# feld_hw.net
KiCad netlist of a schematic drawn in EAGLE
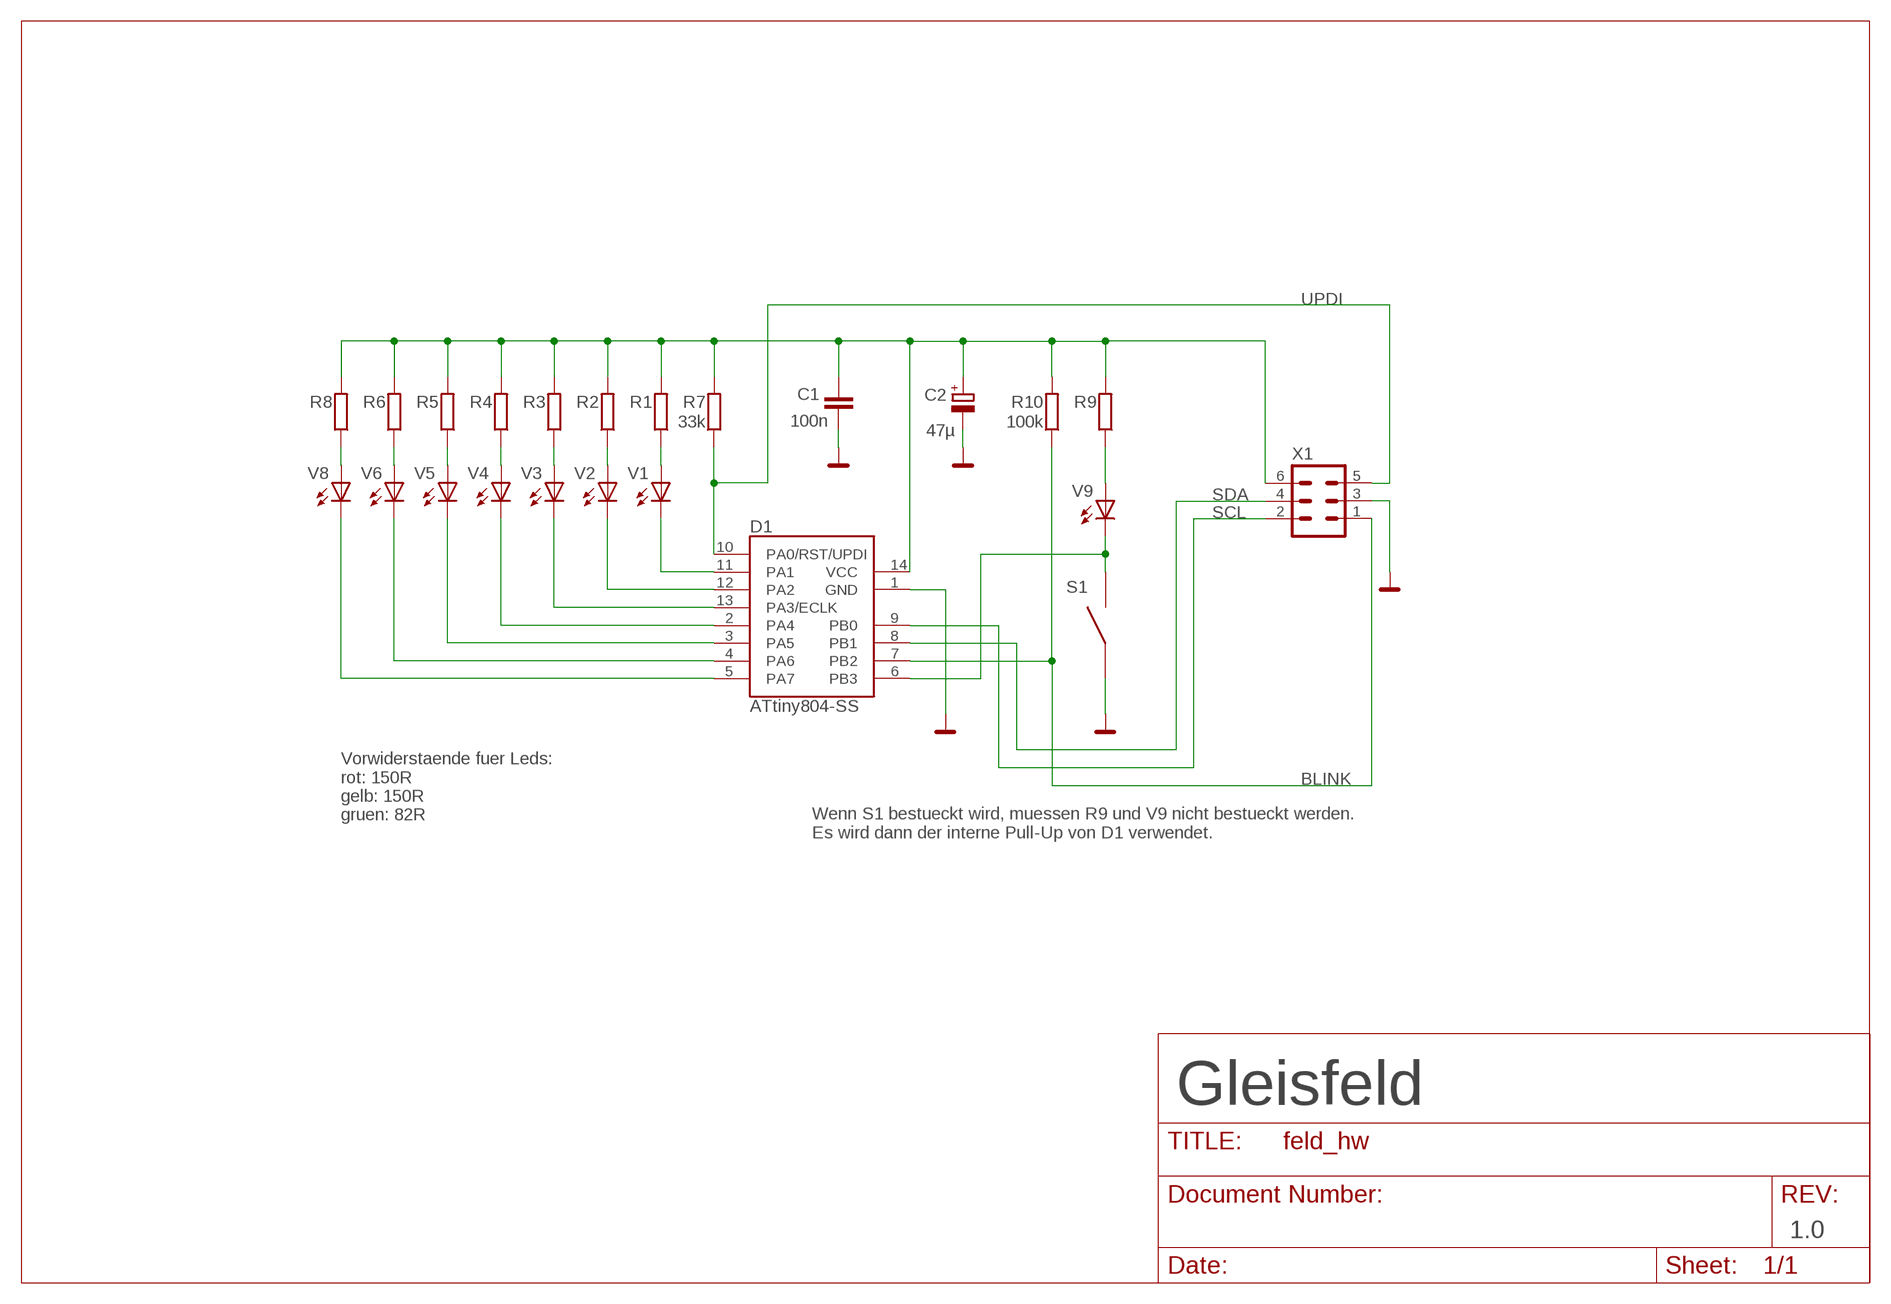
[diagram p0: schematic, sheet 1]

(export (version "E")
  (design (tool "Eeschema 10.0.6"))
  (components
    (comp (ref "C1")
      (value "100n")
      (footprint "eagle-import:C0805")
      (libsource (lib "eagle-import") (part "C-EUC0805"))
    )
    (comp (ref "C2")
      (value "47µ")
      (footprint "eagle-import:CT7343")
      (libsource (lib "eagle-import") (part "CPOL-EUCT7343"))
    )
    (comp (ref "D1")
      (value "ATtiny804-SS")
      (footprint "eagle-import:SOIC14")
      (libsource (lib "eagle-import") (part "ATTINY204"))
    )
    (comp (ref "R1")
      (value "R-EU_R0805")
      (footprint "eagle-import:R0805")
      (libsource (lib "eagle-import") (part "R-EU_R0805"))
    )
    (comp (ref "R2")
      (value "R-EU_R0805")
      (footprint "eagle-import:R0805")
      (libsource (lib "eagle-import") (part "R-EU_R0805"))
    )
    (comp (ref "R3")
      (value "R-EU_R0805")
      (footprint "eagle-import:R0805")
      (libsource (lib "eagle-import") (part "R-EU_R0805"))
    )
    (comp (ref "R4")
      (value "R-EU_R0805")
      (footprint "eagle-import:R0805")
      (libsource (lib "eagle-import") (part "R-EU_R0805"))
    )
    (comp (ref "R5")
      (value "R-EU_R0805")
      (footprint "eagle-import:R0805")
      (libsource (lib "eagle-import") (part "R-EU_R0805"))
    )
    (comp (ref "R6")
      (value "R-EU_R0805")
      (footprint "eagle-import:R0805")
      (libsource (lib "eagle-import") (part "R-EU_R0805"))
    )
    (comp (ref "R7")
      (value "33k")
      (footprint "eagle-import:R0805")
      (libsource (lib "eagle-import") (part "R-EU_R0805"))
    )
    (comp (ref "R8")
      (value "R-EU_R0805")
      (footprint "eagle-import:R0805")
      (libsource (lib "eagle-import") (part "R-EU_R0805"))
    )
    (comp (ref "R9")
      (value "R-EU_R0805")
      (footprint "eagle-import:R0805")
      (libsource (lib "eagle-import") (part "R-EU_R0805"))
    )
    (comp (ref "R10")
      (value "100k")
      (footprint "eagle-import:R0805")
      (libsource (lib "eagle-import") (part "R-EU_R0805"))
    )
    (comp (ref "S1")
      (value "800SP9B5M2QEH")
      (footprint "eagle-import:ST811004")
      (libsource (lib "eagle-import") (part "800SP9B5M2QEH"))
    )
    (comp (ref "V1")
      (value "LEDPAD")
      (footprint "eagle-import:LED3MMPAD")
      (libsource (lib "eagle-import") (part "LEDPAD"))
    )
    (comp (ref "V2")
      (value "LEDPAD")
      (footprint "eagle-import:LED3MMPAD")
      (libsource (lib "eagle-import") (part "LEDPAD"))
    )
    (comp (ref "V3")
      (value "LEDPAD")
      (footprint "eagle-import:LED3MMPAD")
      (libsource (lib "eagle-import") (part "LEDPAD"))
    )
    (comp (ref "V4")
      (value "LEDPAD")
      (footprint "eagle-import:LED3MMPAD")
      (libsource (lib "eagle-import") (part "LEDPAD"))
    )
    (comp (ref "V5")
      (value "LEDPAD")
      (footprint "eagle-import:LED3MMPAD")
      (libsource (lib "eagle-import") (part "LEDPAD"))
    )
    (comp (ref "V6")
      (value "LEDPAD")
      (footprint "eagle-import:LED3MMPAD")
      (libsource (lib "eagle-import") (part "LEDPAD"))
    )
    (comp (ref "V8")
      (value "LEDPAD")
      (footprint "eagle-import:LED3MMPAD")
      (libsource (lib "eagle-import") (part "LEDPAD"))
    )
    (comp (ref "V9")
      (value "LEDPAD")
      (footprint "eagle-import:LED3MMPAD")
      (libsource (lib "eagle-import") (part "LEDPAD"))
    )
    (comp (ref "X1")
      (value "PINH2X3N")
      (footprint "eagle-import:MA03_2")
      (libsource (lib "eagle-import") (part "PINH2X3N"))
    )
  )
  (nets
    (net (code "1") (name "/BLINK") (class "Default")
      (node (ref "D1") (pin "7") (pinfunction "PB2_7") (pintype "bidirectional"))
      (node (ref "R10") (pin "1") (pinfunction "1_1") (pintype "passive"))
      (node (ref "X1") (pin "1") (pinfunction "1_1") (pintype "passive"))
    )
    (net (code "2") (name "/SCL") (class "Default")
      (node (ref "D1") (pin "9") (pinfunction "PB0_9") (pintype "bidirectional"))
      (node (ref "X1") (pin "2") (pinfunction "2_2") (pintype "passive"))
    )
    (net (code "3") (name "/SDA") (class "Default")
      (node (ref "D1") (pin "8") (pinfunction "PB1_8") (pintype "bidirectional"))
      (node (ref "X1") (pin "4") (pinfunction "4_4") (pintype "passive"))
    )
    (net (code "4") (name "/UPDI") (class "Default")
      (node (ref "D1") (pin "10") (pinfunction "PA0/RST/UPDI_10") (pintype "bidirectional"))
      (node (ref "R7") (pin "1") (pinfunction "1_1") (pintype "passive"))
      (node (ref "X1") (pin "5") (pinfunction "5_5") (pintype "passive"))
    )
    (net (code "5") (name "GND") (class "Default")
      (node (ref "C1") (pin "1") (pinfunction "1_1") (pintype "passive"))
      (node (ref "C2") (pin "-") (pinfunction "-_-") (pintype "passive"))
      (node (ref "D1") (pin "1") (pinfunction "GND_1") (pintype "power_in"))
      (node (ref "S1") (pin "1") (pinfunction "1_1") (pintype "passive"))
      (node (ref "X1") (pin "3") (pinfunction "3_3") (pintype "passive"))
    )
    (net (code "6") (name "Net-(D1-PA1)") (class "Default")
      (node (ref "D1") (pin "11") (pinfunction "PA1_11") (pintype "bidirectional"))
      (node (ref "V1") (pin "P$2") (pinfunction "C_P$2") (pintype "passive"))
    )
    (net (code "7") (name "Net-(D1-PA2)") (class "Default")
      (node (ref "D1") (pin "12") (pinfunction "PA2_12") (pintype "bidirectional"))
      (node (ref "V2") (pin "P$2") (pinfunction "C_P$2") (pintype "passive"))
    )
    (net (code "8") (name "Net-(D1-PA3{slash}ECLK)") (class "Default")
      (node (ref "D1") (pin "13") (pinfunction "PA3/ECLK_13") (pintype "bidirectional"))
      (node (ref "V3") (pin "P$2") (pinfunction "C_P$2") (pintype "passive"))
    )
    (net (code "9") (name "Net-(D1-PA4)") (class "Default")
      (node (ref "D1") (pin "2") (pinfunction "PA4_2") (pintype "bidirectional"))
      (node (ref "V4") (pin "P$2") (pinfunction "C_P$2") (pintype "passive"))
    )
    (net (code "10") (name "Net-(D1-PA5)") (class "Default")
      (node (ref "D1") (pin "3") (pinfunction "PA5_3") (pintype "bidirectional"))
      (node (ref "V5") (pin "P$2") (pinfunction "C_P$2") (pintype "passive"))
    )
    (net (code "11") (name "Net-(D1-PA6)") (class "Default")
      (node (ref "D1") (pin "4") (pinfunction "PA6_4") (pintype "bidirectional"))
      (node (ref "V6") (pin "P$2") (pinfunction "C_P$2") (pintype "passive"))
    )
    (net (code "12") (name "Net-(D1-PA7)") (class "Default")
      (node (ref "D1") (pin "5") (pinfunction "PA7_5") (pintype "bidirectional"))
      (node (ref "V8") (pin "P$2") (pinfunction "C_P$2") (pintype "passive"))
    )
    (net (code "13") (name "Net-(D1-PB3)") (class "Default")
      (node (ref "D1") (pin "6") (pinfunction "PB3_6") (pintype "bidirectional"))
      (node (ref "S1") (pin "2") (pinfunction "2_2") (pintype "passive"))
      (node (ref "V9") (pin "P$2") (pinfunction "C_P$2") (pintype "passive"))
    )
    (net (code "14") (name "Net-(D1-VCC)") (class "Default")
      (node (ref "C1") (pin "2") (pinfunction "2_2") (pintype "passive"))
      (node (ref "C2") (pin "+") (pinfunction "+_+") (pintype "passive"))
      (node (ref "D1") (pin "14") (pinfunction "VCC_14") (pintype "power_in"))
      (node (ref "R1") (pin "2") (pinfunction "2_2") (pintype "passive"))
      (node (ref "R10") (pin "2") (pinfunction "2_2") (pintype "passive"))
      (node (ref "R2") (pin "2") (pinfunction "2_2") (pintype "passive"))
      (node (ref "R3") (pin "2") (pinfunction "2_2") (pintype "passive"))
      (node (ref "R4") (pin "2") (pinfunction "2_2") (pintype "passive"))
      (node (ref "R5") (pin "2") (pinfunction "2_2") (pintype "passive"))
      (node (ref "R6") (pin "2") (pinfunction "2_2") (pintype "passive"))
      (node (ref "R7") (pin "2") (pinfunction "2_2") (pintype "passive"))
      (node (ref "R8") (pin "2") (pinfunction "2_2") (pintype "passive"))
      (node (ref "R9") (pin "2") (pinfunction "2_2") (pintype "passive"))
      (node (ref "X1") (pin "6") (pinfunction "6_6") (pintype "passive"))
    )
    (net (code "15") (name "Net-(V1-A)") (class "Default")
      (node (ref "R1") (pin "1") (pinfunction "1_1") (pintype "passive"))
      (node (ref "V1") (pin "P$1") (pinfunction "A_P$1") (pintype "passive"))
    )
    (net (code "16") (name "Net-(V2-A)") (class "Default")
      (node (ref "R2") (pin "1") (pinfunction "1_1") (pintype "passive"))
      (node (ref "V2") (pin "P$1") (pinfunction "A_P$1") (pintype "passive"))
    )
    (net (code "17") (name "Net-(V3-A)") (class "Default")
      (node (ref "R3") (pin "1") (pinfunction "1_1") (pintype "passive"))
      (node (ref "V3") (pin "P$1") (pinfunction "A_P$1") (pintype "passive"))
    )
    (net (code "18") (name "Net-(V4-A)") (class "Default")
      (node (ref "R4") (pin "1") (pinfunction "1_1") (pintype "passive"))
      (node (ref "V4") (pin "P$1") (pinfunction "A_P$1") (pintype "passive"))
    )
    (net (code "19") (name "Net-(V5-A)") (class "Default")
      (node (ref "R5") (pin "1") (pinfunction "1_1") (pintype "passive"))
      (node (ref "V5") (pin "P$1") (pinfunction "A_P$1") (pintype "passive"))
    )
    (net (code "20") (name "Net-(V6-A)") (class "Default")
      (node (ref "R6") (pin "1") (pinfunction "1_1") (pintype "passive"))
      (node (ref "V6") (pin "P$1") (pinfunction "A_P$1") (pintype "passive"))
    )
    (net (code "21") (name "Net-(V8-A)") (class "Default")
      (node (ref "R8") (pin "1") (pinfunction "1_1") (pintype "passive"))
      (node (ref "V8") (pin "P$1") (pinfunction "A_P$1") (pintype "passive"))
    )
    (net (code "22") (name "Net-(V9-A)") (class "Default")
      (node (ref "R9") (pin "1") (pinfunction "1_1") (pintype "passive"))
      (node (ref "V9") (pin "P$1") (pinfunction "A_P$1") (pintype "passive"))
    )
  )
)
